# PennyMan_Ard_R3_Shield_v5_2.net
KiCad netlist of a schematic drawn in EAGLE
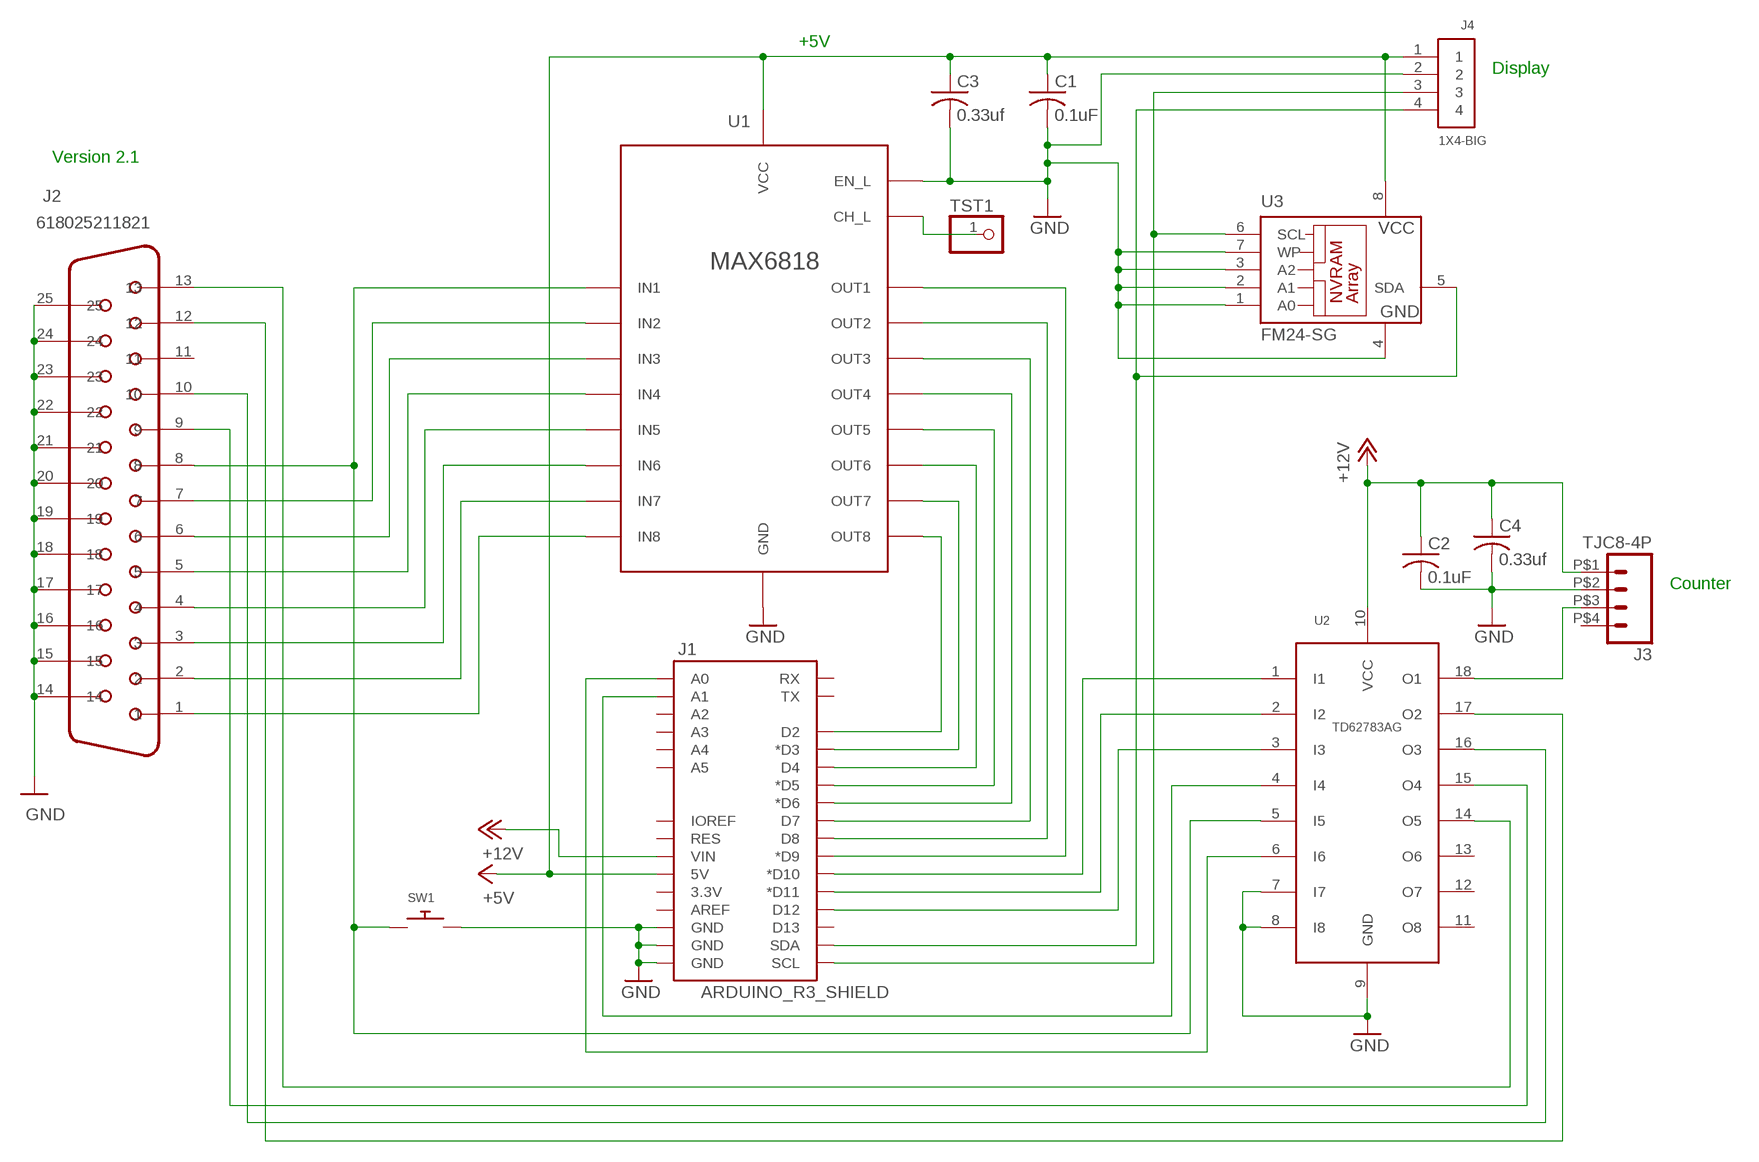
[diagram p0: schematic, sheet 1]

(export (version "E")
  (design (tool "Eeschema 10.0.6"))
  (components
    (comp (ref "C1")
      (value "0.1uF")
      (footprint "eagle-import:C0805")
      (libsource (lib "eagle-import") (part "C-USC0805"))
    )
    (comp (ref "C2")
      (value "0.1uF")
      (footprint "eagle-import:C0805")
      (libsource (lib "eagle-import") (part "C-USC0805"))
    )
    (comp (ref "C3")
      (value "0.33uf")
      (footprint "eagle-import:C1206")
      (libsource (lib "eagle-import") (part "C-USC1206"))
    )
    (comp (ref "C4")
      (value "0.33uf")
      (footprint "eagle-import:C1206")
      (libsource (lib "eagle-import") (part "C-USC1206"))
    )
    (comp (ref "J1")
      (value "ARDUINO_R3_SHIELD")
      (footprint "eagle-import:UNO_R3_SHIELD")
      (libsource (lib "eagle-import") (part "ARDUINO_R3_SHIELD"))
    )
    (comp (ref "J2")
      (value "618025211821")
      (footprint "eagle-import:618025211821")
      (libsource (lib "eagle-import") (part "618025211821"))
    )
    (comp (ref "J3")
      (value "TJC8-4P")
      (footprint "eagle-import:TJC8-4P")
      (libsource (lib "eagle-import") (part "TJC8-4P"))
    )
    (comp (ref "J4")
      (value "1X4-BIG")
      (footprint "eagle-import:1X04-BIG")
      (libsource (lib "eagle-import") (part "1X4-BIG"))
    )
    (comp (ref "SW1")
      (value "SWITCH_PUSHBUTTONEVQ-PE")
      (footprint "eagle-import:TACT_PANA-EVQ")
      (libsource (lib "eagle-import") (part "SWITCH_PUSHBUTTONEVQ-PE"))
    )
    (comp (ref "TST1")
      (value "PINHD-1X1")
      (footprint "eagle-import:1X01")
      (libsource (lib "eagle-import") (part "PINHD-1X1"))
    )
    (comp (ref "U1")
      (value "MAX6818")
      (footprint "eagle-import:SSOP20")
      (libsource (lib "eagle-import") (part "MAX6818"))
    )
    (comp (ref "U2")
      (value "TD62783AG")
      (footprint "eagle-import:SOP18")
      (libsource (lib "eagle-import") (part "TD62783AG"))
    )
    (comp (ref "U3")
      (value "FM24-SG")
      (footprint "eagle-import:SO8")
      (libsource (lib "eagle-import") (part "FM24-SG"))
    )
  )
  (nets
    (net (code "1") (name "+5V") (class "Default")
      (node (ref "C1") (pin "1") (pinfunction "1_1") (pintype "passive"))
      (node (ref "C3") (pin "1") (pinfunction "1_1") (pintype "passive"))
      (node (ref "J1") (pin "5V") (pinfunction "5V_5V") (pintype "bidirectional"))
      (node (ref "J4") (pin "1") (pinfunction "1_1") (pintype "bidirectional"))
      (node (ref "U1") (pin "VCC") (pinfunction "VCC_VCC") (pintype "bidirectional"))
      (node (ref "U3") (pin "8") (pinfunction "VCC_8") (pintype "power_in"))
    )
    (net (code "2") (name "+12V") (class "Default")
      (node (ref "C2") (pin "1") (pinfunction "1_1") (pintype "passive"))
      (node (ref "C4") (pin "1") (pinfunction "1_1") (pintype "passive"))
      (node (ref "J1") (pin "VIN") (pinfunction "VIN_VIN") (pintype "bidirectional"))
      (node (ref "J3") (pin "P$1") (pinfunction "1_P$1") (pintype "passive"))
      (node (ref "U2") (pin "10") (pinfunction "VCC_10") (pintype "bidirectional"))
    )
    (net (code "3") (name "GND") (class "Default")
      (node (ref "C1") (pin "2") (pinfunction "2_2") (pintype "passive"))
      (node (ref "C2") (pin "2") (pinfunction "2_2") (pintype "passive"))
      (node (ref "C3") (pin "2") (pinfunction "2_2") (pintype "passive"))
      (node (ref "C4") (pin "2") (pinfunction "2_2") (pintype "passive"))
      (node (ref "J1") (pin "GND@0") (pinfunction "GND_GND@0") (pintype "bidirectional"))
      (node (ref "J1") (pin "GND@1") (pinfunction "GND_GND@1") (pintype "bidirectional"))
      (node (ref "J1") (pin "GND@2") (pinfunction "GND_GND@2") (pintype "bidirectional"))
      (node (ref "J2") (pin "14") (pinfunction "14_14") (pintype "bidirectional"))
      (node (ref "J2") (pin "15") (pinfunction "15_15") (pintype "bidirectional"))
      (node (ref "J2") (pin "16") (pinfunction "16_16") (pintype "bidirectional"))
      (node (ref "J2") (pin "17") (pinfunction "17_17") (pintype "bidirectional"))
      (node (ref "J2") (pin "18") (pinfunction "18_18") (pintype "bidirectional"))
      (node (ref "J2") (pin "19") (pinfunction "19_19") (pintype "bidirectional"))
      (node (ref "J2") (pin "20") (pinfunction "20_20") (pintype "bidirectional"))
      (node (ref "J2") (pin "21") (pinfunction "21_21") (pintype "bidirectional"))
      (node (ref "J2") (pin "22") (pinfunction "22_22") (pintype "bidirectional"))
      (node (ref "J2") (pin "23") (pinfunction "23_23") (pintype "bidirectional"))
      (node (ref "J2") (pin "24") (pinfunction "24_24") (pintype "bidirectional"))
      (node (ref "J2") (pin "25") (pinfunction "25_25") (pintype "bidirectional"))
      (node (ref "J3") (pin "P$2") (pinfunction "2_P$2") (pintype "passive"))
      (node (ref "J4") (pin "2") (pinfunction "2_2") (pintype "bidirectional"))
      (node (ref "SW1") (pin "P$2") (pinfunction "P$2_P$2") (pintype "passive"))
      (node (ref "U1") (pin "EN_L") (pinfunction "EN_L_EN_L") (pintype "bidirectional"))
      (node (ref "U1") (pin "GND") (pinfunction "GND_GND") (pintype "bidirectional"))
      (node (ref "U2") (pin "7") (pinfunction "I7_7") (pintype "bidirectional"))
      (node (ref "U2") (pin "8") (pinfunction "I8_8") (pintype "bidirectional"))
      (node (ref "U2") (pin "9") (pinfunction "GND_9") (pintype "bidirectional"))
      (node (ref "U3") (pin "1") (pinfunction "A0_1") (pintype "passive"))
      (node (ref "U3") (pin "2") (pinfunction "A1_2") (pintype "passive"))
      (node (ref "U3") (pin "3") (pinfunction "A2_3") (pintype "passive"))
      (node (ref "U3") (pin "4") (pinfunction "GND_4") (pintype "power_in"))
      (node (ref "U3") (pin "7") (pinfunction "WP_7") (pintype "input"))
    )
    (net (code "4") (name "Net-(J1-*D3)") (class "Default")
      (node (ref "J1") (pin "D3") (pinfunction "*D3_D3") (pintype "bidirectional"))
      (node (ref "U1") (pin "OUT7") (pinfunction "OUT7_OUT7") (pintype "bidirectional"))
    )
    (net (code "5") (name "Net-(J1-*D5)") (class "Default")
      (node (ref "J1") (pin "D5") (pinfunction "*D5_D5") (pintype "bidirectional"))
      (node (ref "U1") (pin "OUT5") (pinfunction "OUT5_OUT5") (pintype "bidirectional"))
    )
    (net (code "6") (name "Net-(J1-*D6)") (class "Default")
      (node (ref "J1") (pin "D6") (pinfunction "*D6_D6") (pintype "bidirectional"))
      (node (ref "U1") (pin "OUT4") (pinfunction "OUT4_OUT4") (pintype "bidirectional"))
    )
    (net (code "7") (name "Net-(J1-*D9)") (class "Default")
      (node (ref "J1") (pin "D9") (pinfunction "*D9_D9") (pintype "bidirectional"))
      (node (ref "U1") (pin "OUT1") (pinfunction "OUT1_OUT1") (pintype "bidirectional"))
    )
    (net (code "8") (name "Net-(J1-*D10)") (class "Default")
      (node (ref "J1") (pin "D10") (pinfunction "*D10_D10") (pintype "bidirectional"))
      (node (ref "U2") (pin "1") (pinfunction "I1_1") (pintype "bidirectional"))
    )
    (net (code "9") (name "Net-(J1-*D11)") (class "Default")
      (node (ref "J1") (pin "D11") (pinfunction "*D11_D11") (pintype "bidirectional"))
      (node (ref "U2") (pin "2") (pinfunction "I2_2") (pintype "bidirectional"))
    )
    (net (code "10") (name "Net-(J1-PadD2)") (class "Default")
      (node (ref "J1") (pin "D2") (pinfunction "D2_D2") (pintype "bidirectional"))
      (node (ref "U1") (pin "OUT8") (pinfunction "OUT8_OUT8") (pintype "bidirectional"))
    )
    (net (code "11") (name "Net-(J1-PadD4)") (class "Default")
      (node (ref "J1") (pin "D4") (pinfunction "D4_D4") (pintype "bidirectional"))
      (node (ref "U1") (pin "OUT6") (pinfunction "OUT6_OUT6") (pintype "bidirectional"))
    )
    (net (code "12") (name "Net-(J1-PadD7)") (class "Default")
      (node (ref "J1") (pin "D7") (pinfunction "D7_D7") (pintype "bidirectional"))
      (node (ref "U1") (pin "OUT3") (pinfunction "OUT3_OUT3") (pintype "bidirectional"))
    )
    (net (code "13") (name "Net-(J1-PadD8)") (class "Default")
      (node (ref "J1") (pin "D8") (pinfunction "D8_D8") (pintype "bidirectional"))
      (node (ref "U1") (pin "OUT2") (pinfunction "OUT2_OUT2") (pintype "bidirectional"))
    )
    (net (code "14") (name "Net-(J2-Pad1)") (class "Default")
      (node (ref "J2") (pin "1") (pinfunction "1_1") (pintype "bidirectional"))
      (node (ref "U1") (pin "IN8") (pinfunction "IN8_IN8") (pintype "bidirectional"))
    )
    (net (code "15") (name "Net-(J2-Pad2)") (class "Default")
      (node (ref "J2") (pin "2") (pinfunction "2_2") (pintype "bidirectional"))
      (node (ref "U1") (pin "IN7") (pinfunction "IN7_IN7") (pintype "bidirectional"))
    )
    (net (code "16") (name "Net-(J2-Pad3)") (class "Default")
      (node (ref "J2") (pin "3") (pinfunction "3_3") (pintype "bidirectional"))
      (node (ref "U1") (pin "IN6") (pinfunction "IN6_IN6") (pintype "bidirectional"))
    )
    (net (code "17") (name "Net-(J2-Pad4)") (class "Default")
      (node (ref "J2") (pin "4") (pinfunction "4_4") (pintype "bidirectional"))
      (node (ref "U1") (pin "IN5") (pinfunction "IN5_IN5") (pintype "bidirectional"))
    )
    (net (code "18") (name "Net-(J2-Pad5)") (class "Default")
      (node (ref "J2") (pin "5") (pinfunction "5_5") (pintype "bidirectional"))
      (node (ref "U1") (pin "IN4") (pinfunction "IN4_IN4") (pintype "bidirectional"))
    )
    (net (code "19") (name "Net-(J2-Pad6)") (class "Default")
      (node (ref "J2") (pin "6") (pinfunction "6_6") (pintype "bidirectional"))
      (node (ref "U1") (pin "IN3") (pinfunction "IN3_IN3") (pintype "bidirectional"))
    )
    (net (code "20") (name "Net-(J2-Pad7)") (class "Default")
      (node (ref "J2") (pin "7") (pinfunction "7_7") (pintype "bidirectional"))
      (node (ref "U1") (pin "IN2") (pinfunction "IN2_IN2") (pintype "bidirectional"))
    )
    (net (code "21") (name "Net-(J3-3)") (class "Default")
      (node (ref "J3") (pin "P$3") (pinfunction "3_P$3") (pintype "passive"))
      (node (ref "U2") (pin "18") (pinfunction "O1_18") (pintype "bidirectional"))
    )
    (net (code "22") (name "Net-(TST1-Pad1)") (class "Default")
      (node (ref "TST1") (pin "1") (pinfunction "1_1") (pintype "passive"))
      (node (ref "U1") (pin "CH_L") (pinfunction "CH_L_CH_L") (pintype "bidirectional"))
    )
    (net (code "23") (name "Net-(U2-I3)") (class "Default")
      (node (ref "J1") (pin "D12") (pinfunction "D12_D12") (pintype "bidirectional"))
      (node (ref "U2") (pin "3") (pinfunction "I3_3") (pintype "bidirectional"))
    )
    (net (code "24") (name "Net-(U2-I4)") (class "Default")
      (node (ref "J1") (pin "A1") (pinfunction "A1_A1") (pintype "bidirectional"))
      (node (ref "U2") (pin "4") (pinfunction "I4_4") (pintype "bidirectional"))
    )
    (net (code "25") (name "Net-(U2-I5)") (class "Default")
      (node (ref "J2") (pin "8") (pinfunction "8_8") (pintype "bidirectional"))
      (node (ref "SW1") (pin "P$1") (pinfunction "P$1_P$1") (pintype "passive"))
      (node (ref "U1") (pin "IN1") (pinfunction "IN1_IN1") (pintype "bidirectional"))
      (node (ref "U2") (pin "5") (pinfunction "I5_5") (pintype "bidirectional"))
    )
    (net (code "26") (name "Net-(U2-I6)") (class "Default")
      (node (ref "J1") (pin "A0") (pinfunction "A0_A0") (pintype "bidirectional"))
      (node (ref "U2") (pin "6") (pinfunction "I6_6") (pintype "bidirectional"))
    )
    (net (code "27") (name "Net-(U2-O2)") (class "Default")
      (node (ref "J2") (pin "12") (pinfunction "12_12") (pintype "bidirectional"))
      (node (ref "U2") (pin "17") (pinfunction "O2_17") (pintype "bidirectional"))
    )
    (net (code "28") (name "Net-(U2-O3)") (class "Default")
      (node (ref "J2") (pin "10") (pinfunction "10_10") (pintype "bidirectional"))
      (node (ref "U2") (pin "16") (pinfunction "O3_16") (pintype "bidirectional"))
    )
    (net (code "29") (name "Net-(U2-O4)") (class "Default")
      (node (ref "J2") (pin "9") (pinfunction "9_9") (pintype "bidirectional"))
      (node (ref "U2") (pin "15") (pinfunction "O4_15") (pintype "bidirectional"))
    )
    (net (code "30") (name "Net-(U2-O5)") (class "Default")
      (node (ref "J2") (pin "13") (pinfunction "13_13") (pintype "bidirectional"))
      (node (ref "U2") (pin "14") (pinfunction "O5_14") (pintype "bidirectional"))
    )
    (net (code "31") (name "Net-(U3-SCL)") (class "Default")
      (node (ref "J1") (pin "SCL") (pinfunction "SCL_SCL") (pintype "bidirectional"))
      (node (ref "J4") (pin "3") (pinfunction "3_3") (pintype "bidirectional"))
      (node (ref "U3") (pin "6") (pinfunction "SCL_6") (pintype "input"))
    )
    (net (code "32") (name "Net-(U3-SDA)") (class "Default")
      (node (ref "J1") (pin "SDA") (pinfunction "SDA_SDA") (pintype "bidirectional"))
      (node (ref "J4") (pin "4") (pinfunction "4_4") (pintype "bidirectional"))
      (node (ref "U3") (pin "5") (pinfunction "SDA_5") (pintype "bidirectional"))
    )
    (net (code "33") (name "unconnected-(J1-Pad3.3V)") (class "Default")
      (node (ref "J1") (pin "3.3V") (pinfunction "3.3V_3.3V") (pintype "bidirectional"))
    )
    (net (code "34") (name "unconnected-(J1-PadA2)") (class "Default")
      (node (ref "J1") (pin "A2") (pinfunction "A2_A2") (pintype "bidirectional"))
    )
    (net (code "35") (name "unconnected-(J1-PadA3)") (class "Default")
      (node (ref "J1") (pin "A3") (pinfunction "A3_A3") (pintype "bidirectional"))
    )
    (net (code "36") (name "unconnected-(J1-PadA4)") (class "Default")
      (node (ref "J1") (pin "A4") (pinfunction "A4_A4") (pintype "bidirectional"))
    )
    (net (code "37") (name "unconnected-(J1-PadA5)") (class "Default")
      (node (ref "J1") (pin "A5") (pinfunction "A5_A5") (pintype "bidirectional"))
    )
    (net (code "38") (name "unconnected-(J1-PadAREF)") (class "Default")
      (node (ref "J1") (pin "AREF") (pinfunction "AREF_AREF") (pintype "bidirectional"))
    )
    (net (code "39") (name "unconnected-(J1-PadD13)") (class "Default")
      (node (ref "J1") (pin "D13") (pinfunction "D13_D13") (pintype "bidirectional"))
    )
    (net (code "40") (name "unconnected-(J1-PadIOREF)") (class "Default")
      (node (ref "J1") (pin "IOREF") (pinfunction "IOREF_IOREF") (pintype "bidirectional"))
    )
    (net (code "41") (name "unconnected-(J1-PadRES)") (class "Default")
      (node (ref "J1") (pin "RES") (pinfunction "RES_RES") (pintype "bidirectional"))
    )
    (net (code "42") (name "unconnected-(J1-PadRX)") (class "Default")
      (node (ref "J1") (pin "RX") (pinfunction "RX_RX") (pintype "bidirectional"))
    )
    (net (code "43") (name "unconnected-(J1-PadTX)") (class "Default")
      (node (ref "J1") (pin "TX") (pinfunction "TX_TX") (pintype "bidirectional"))
    )
    (net (code "44") (name "unconnected-(J2-Pad11)") (class "Default")
      (node (ref "J2") (pin "11") (pinfunction "11_11") (pintype "bidirectional"))
    )
    (net (code "45") (name "unconnected-(J3-4-PadP$4)") (class "Default")
      (node (ref "J3") (pin "P$4") (pinfunction "4_P$4") (pintype "passive"))
    )
    (net (code "46") (name "unconnected-(U2-O6-Pad13)") (class "Default")
      (node (ref "U2") (pin "13") (pinfunction "O6_13") (pintype "bidirectional"))
    )
    (net (code "47") (name "unconnected-(U2-O7-Pad12)") (class "Default")
      (node (ref "U2") (pin "12") (pinfunction "O7_12") (pintype "bidirectional"))
    )
    (net (code "48") (name "unconnected-(U2-O8-Pad11)") (class "Default")
      (node (ref "U2") (pin "11") (pinfunction "O8_11") (pintype "bidirectional"))
    )
  )
)
